# com.net
KiCad netlist of a schematic drawn in Altium Designer
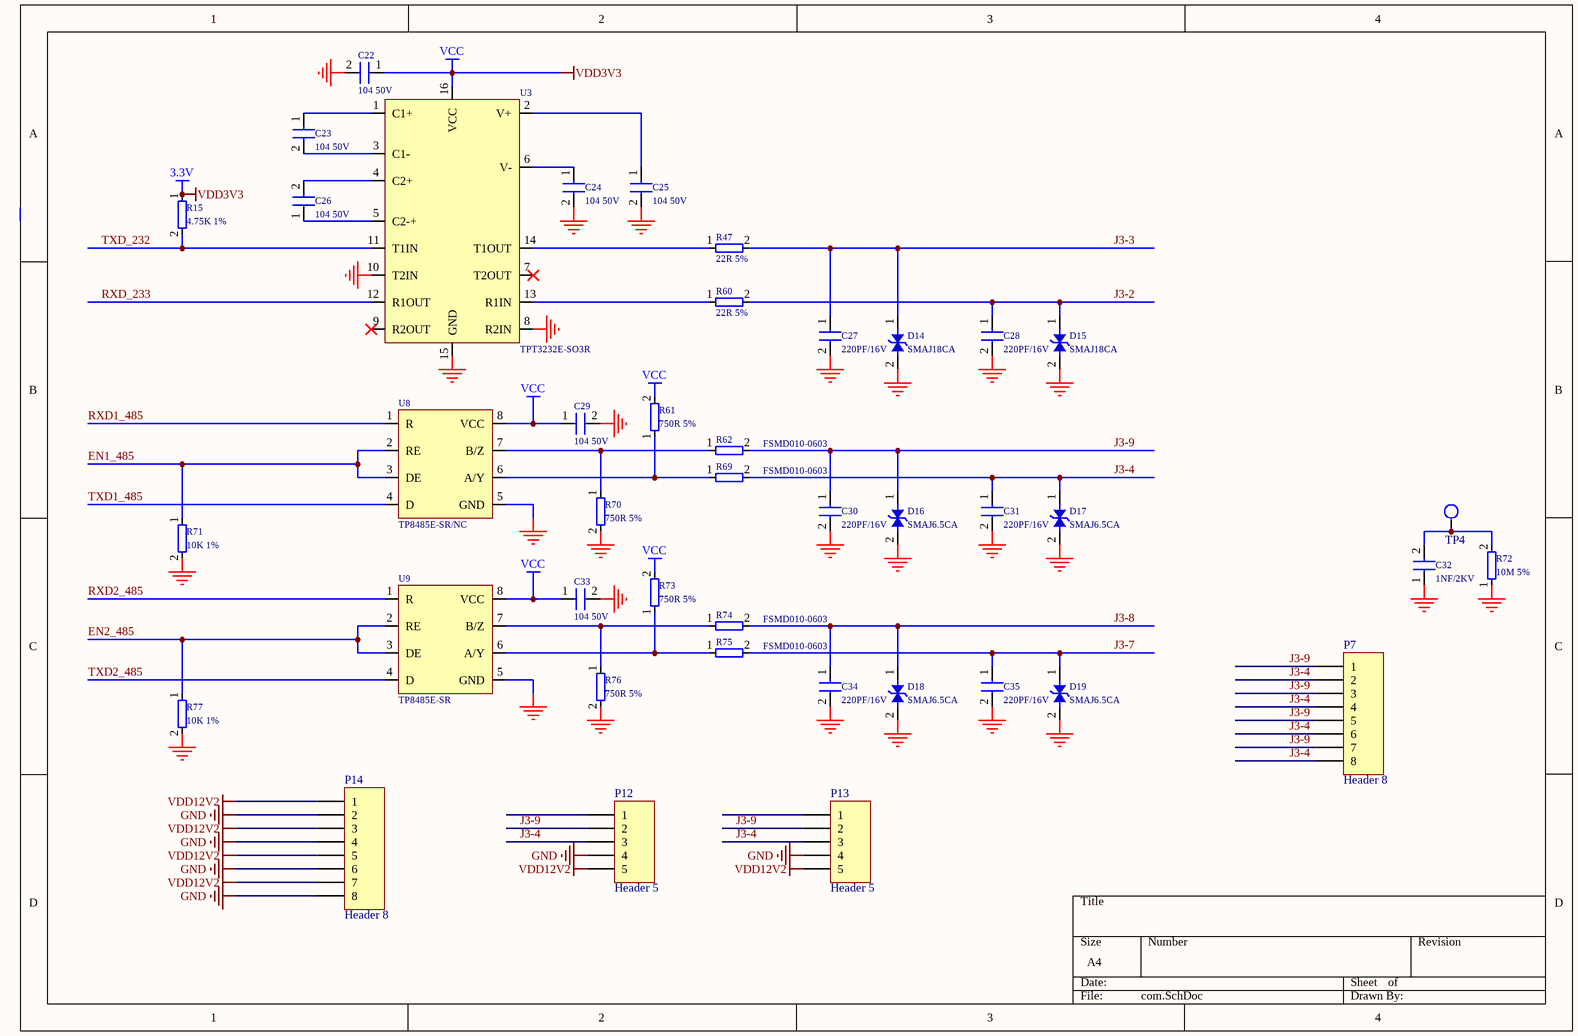
[diagram p0: com.SchDoc]

(export (version "E")
  (design (tool "Eeschema 10.0.6"))
  (components
    (comp (ref "C22") (value "104 50V") (footprint "0603C") (libsource (lib "*") (part "CAP")))
    (comp (ref "C23") (value "104 50V") (footprint "0603C") (libsource (lib "*") (part "CAP")))
    (comp (ref "C24") (value "104 50V") (footprint "0603C") (libsource (lib "*") (part "CAP")))
    (comp (ref "C25") (value "104 50V") (footprint "0603C") (libsource (lib "*") (part "CAP")))
    (comp (ref "C26") (value "104 50V") (footprint "0603C") (libsource (lib "*") (part "CAP")))
    (comp (ref "C27") (value "220PF/16V") (footprint "0603C") (libsource (lib "*") (part "CAP")))
    (comp (ref "C28") (value "220PF/16V") (footprint "0603C") (libsource (lib "*") (part "CAP")))
    (comp (ref "C29") (value "104 50V") (footprint "0603C") (libsource (lib "*") (part "CAP")))
    (comp (ref "C30") (value "220PF/16V") (footprint "0603C") (libsource (lib "*") (part "CAP")))
    (comp (ref "C31") (value "220PF/16V") (footprint "0603C") (libsource (lib "*") (part "CAP")))
    (comp (ref "C32") (value "1NF/2KV") (footprint "1206C") (libsource (lib "*") (part "CAP")))
    (comp (ref "C33") (value "104 50V") (footprint "0603C") (libsource (lib "*") (part "CAP")))
    (comp (ref "C34") (value "220PF/16V") (footprint "0603C") (libsource (lib "*") (part "CAP")))
    (comp (ref "C35") (value "220PF/16V") (footprint "0603C") (libsource (lib "*") (part "CAP")))
    (comp (ref "D14") (value "SMAJ18CA") (footprint "SMA") (libsource (lib "*") (part "D_ESD")))
    (comp (ref "D15") (value "SMAJ18CA") (footprint "SMA") (libsource (lib "*") (part "D_ESD")))
    (comp (ref "D16") (value "SMAJ6.5CA") (footprint "SMA") (libsource (lib "*") (part "D_ESD")))
    (comp (ref "D17") (value "SMAJ6.5CA") (footprint "SMA") (libsource (lib "*") (part "D_ESD")))
    (comp (ref "D18") (value "SMAJ6.5CA") (footprint "SMA") (libsource (lib "*") (part "D_ESD")))
    (comp (ref "D19") (value "SMAJ6.5CA") (footprint "SMA") (libsource (lib "*") (part "D_ESD")))
    (comp (ref "P7")
      (value "Header 8")
      (footprint "8X2.54MMZ")
      (description "Header, 8-Pin")
      (fields (field (name "PUBLISHER") "Altium Limited"))
      (libsource (lib "Miscellaneous Connectors") (part "Header 8"))
    )
    (comp (ref "P12")
      (value "Header 5")
      (footprint "5X2.54MMZ")
      (description "Header, 5-Pin")
      (fields (field (name "PUBLISHER") "Altium Limited"))
      (libsource (lib "Miscellaneous Connectors") (part "Header 5"))
    )
    (comp (ref "P13")
      (value "Header 5")
      (footprint "5X2.54MMZ")
      (description "Header, 5-Pin")
      (fields (field (name "PUBLISHER") "Altium Limited"))
      (libsource (lib "Miscellaneous Connectors") (part "Header 5"))
    )
    (comp (ref "P14")
      (value "Header 8")
      (footprint "电解模块主控板_V1.1_ZM_202109181:8X2.54MMZ")
      (description "Header, 8-Pin")
      (fields (field (name "PUBLISHER") "Altium Limited"))
      (libsource (lib "Miscellaneous Connectors") (part "Header 8"))
    )
    (comp (ref "R15") (value "4.75K 1%") (footprint "0603R") (libsource (lib "*") (part "RES")))
    (comp (ref "R47") (value "22R 5%") (footprint "0603R") (libsource (lib "*") (part "RES")))
    (comp (ref "R60") (value "22R 5%") (footprint "0603R") (libsource (lib "*") (part "RES")))
    (comp (ref "R61") (value "750R 5%") (footprint "0603R") (libsource (lib "*") (part "RES")))
    (comp (ref "R62") (value "FSMD010-0603") (footprint "0603R") (libsource (lib "*") (part "RES")))
    (comp (ref "R69") (value "FSMD010-0603") (footprint "0603R") (libsource (lib "*") (part "RES")))
    (comp (ref "R70") (value "750R 5%") (footprint "0603R") (libsource (lib "*") (part "RES")))
    (comp (ref "R71") (value "10K 1%") (footprint "0603R") (libsource (lib "*") (part "RES")))
    (comp (ref "R72") (value "10M 5%") (footprint "1206r") (libsource (lib "*") (part "RES")))
    (comp (ref "R73") (value "750R 5%") (footprint "0603R") (libsource (lib "*") (part "RES")))
    (comp (ref "R74") (value "FSMD010-0603") (footprint "0603R") (libsource (lib "*") (part "RES")))
    (comp (ref "R75") (value "FSMD010-0603") (footprint "0603R") (libsource (lib "*") (part "RES")))
    (comp (ref "R76") (value "750R 5%") (footprint "0603R") (libsource (lib "*") (part "RES")))
    (comp (ref "R77") (value "10K 1%") (footprint "0603R") (libsource (lib "*") (part "RES")))
    (comp (ref "TP4") (value "TPS") (footprint "tpd") (libsource (lib "stm32") (part "TPS")))
    (comp (ref "U3")
      (value "TPT3232E-SO3R")
      (footprint "SO-16Z")
      (libsource (lib "*") (part "TPT3232E-SO3R"))
    )
    (comp (ref "U8") (value "TP8485E-SR/NC") (footprint "SO-8") (libsource (lib "*") (part "TP8485E-SR")))
    (comp (ref "U9") (value "TP8485E-SR") (footprint "SO-8") (libsource (lib "*") (part "TP8485E-SR")))
  )
  (nets
    (net (code "1") (name "/EN1_485") (class "Default")
      (node (ref "R71") (pin "1") (pinfunction "1_1") (pintype "passive"))
      (node (ref "U8") (pin "2") (pinfunction "RE_2") (pintype "passive"))
      (node (ref "U8") (pin "3") (pinfunction "DE_3") (pintype "passive"))
    )
    (net (code "2") (name "/EN2_485") (class "Default")
      (node (ref "R77") (pin "1") (pinfunction "1_1") (pintype "passive"))
      (node (ref "U9") (pin "2") (pinfunction "RE_2") (pintype "passive"))
      (node (ref "U9") (pin "3") (pinfunction "DE_3") (pintype "passive"))
    )
    (net (code "3") (name "/J3-2") (class "Default")
      (node (ref "C28") (pin "1") (pintype "passive"))
      (node (ref "D15") (pin "1") (pintype "passive"))
      (node (ref "R60") (pin "2") (pinfunction "2_2") (pintype "passive"))
    )
    (net (code "4") (name "/J3-3") (class "Default")
      (node (ref "C27") (pin "1") (pintype "passive"))
      (node (ref "D14") (pin "1") (pintype "passive"))
      (node (ref "R47") (pin "2") (pinfunction "2_2") (pintype "passive"))
    )
    (net (code "5") (name "/J3-4") (class "Default")
      (node (ref "C31") (pin "1") (pintype "passive"))
      (node (ref "D17") (pin "1") (pintype "passive"))
      (node (ref "P12") (pin "3") (pinfunction "3_3") (pintype "passive"))
      (node (ref "P13") (pin "3") (pinfunction "3_3") (pintype "passive"))
      (node (ref "P7") (pin "2") (pinfunction "2_2") (pintype "passive"))
      (node (ref "P7") (pin "4") (pinfunction "4_4") (pintype "passive"))
      (node (ref "P7") (pin "6") (pinfunction "6_6") (pintype "passive"))
      (node (ref "P7") (pin "8") (pinfunction "8_8") (pintype "passive"))
      (node (ref "R69") (pin "2") (pinfunction "2_2") (pintype "passive"))
    )
    (net (code "6") (name "/J3-7") (class "Default")
      (node (ref "C35") (pin "1") (pintype "passive"))
      (node (ref "D19") (pin "1") (pintype "passive"))
      (node (ref "R75") (pin "2") (pinfunction "2_2") (pintype "passive"))
    )
    (net (code "7") (name "/J3-8") (class "Default")
      (node (ref "C34") (pin "1") (pintype "passive"))
      (node (ref "D18") (pin "1") (pintype "passive"))
      (node (ref "R74") (pin "2") (pinfunction "2_2") (pintype "passive"))
    )
    (net (code "8") (name "/J3-9") (class "Default")
      (node (ref "C30") (pin "1") (pintype "passive"))
      (node (ref "D16") (pin "1") (pintype "passive"))
      (node (ref "P12") (pin "2") (pinfunction "2_2") (pintype "passive"))
      (node (ref "P13") (pin "2") (pinfunction "2_2") (pintype "passive"))
      (node (ref "P7") (pin "1") (pinfunction "1_1") (pintype "passive"))
      (node (ref "P7") (pin "3") (pinfunction "3_3") (pintype "passive"))
      (node (ref "P7") (pin "5") (pinfunction "5_5") (pintype "passive"))
      (node (ref "P7") (pin "7") (pinfunction "7_7") (pintype "passive"))
      (node (ref "R62") (pin "2") (pinfunction "2_2") (pintype "passive"))
    )
    (net (code "9") (name "/RXD1_485") (class "Default")
      (node (ref "U8") (pin "1") (pinfunction "R_1") (pintype "passive"))
    )
    (net (code "10") (name "/RXD2_485") (class "Default")
      (node (ref "U9") (pin "1") (pinfunction "R_1") (pintype "passive"))
    )
    (net (code "11") (name "/RXD_233") (class "Default")
      (node (ref "U3") (pin "12") (pinfunction "R1OUT_12") (pintype "passive"))
    )
    (net (code "12") (name "/TXD1_485") (class "Default")
      (node (ref "U8") (pin "4") (pinfunction "D_4") (pintype "passive"))
    )
    (net (code "13") (name "/TXD2_485") (class "Default")
      (node (ref "U9") (pin "4") (pinfunction "D_4") (pintype "passive"))
    )
    (net (code "14") (name "/TXD_232") (class "Default")
      (node (ref "R15") (pin "2") (pinfunction "2_2") (pintype "passive"))
      (node (ref "U3") (pin "11") (pinfunction "T1IN_11") (pintype "passive"))
    )
    (net (code "15") (name "3.3V") (class "Default")
      (node (ref "C22") (pin "1") (pintype "passive"))
      (node (ref "C29") (pin "1") (pintype "passive"))
      (node (ref "C33") (pin "1") (pintype "passive"))
      (node (ref "R15") (pin "1") (pinfunction "1_1") (pintype "passive"))
      (node (ref "R61") (pin "2") (pinfunction "2_2") (pintype "passive"))
      (node (ref "R73") (pin "2") (pinfunction "2_2") (pintype "passive"))
      (node (ref "U3") (pin "16") (pinfunction "VCC_16") (pintype "passive"))
      (node (ref "U8") (pin "8") (pinfunction "VCC_8") (pintype "passive"))
      (node (ref "U9") (pin "8") (pinfunction "VCC_8") (pintype "passive"))
    )
    (net (code "16") (name "GND") (class "Default")
      (node (ref "C22") (pin "2") (pintype "passive"))
      (node (ref "C24") (pin "2") (pintype "passive"))
      (node (ref "C25") (pin "2") (pintype "passive"))
      (node (ref "C27") (pin "2") (pintype "passive"))
      (node (ref "C28") (pin "2") (pintype "passive"))
      (node (ref "C29") (pin "2") (pintype "passive"))
      (node (ref "C30") (pin "2") (pintype "passive"))
      (node (ref "C31") (pin "2") (pintype "passive"))
      (node (ref "C32") (pin "1") (pintype "passive"))
      (node (ref "C33") (pin "2") (pintype "passive"))
      (node (ref "C34") (pin "2") (pintype "passive"))
      (node (ref "C35") (pin "2") (pintype "passive"))
      (node (ref "D14") (pin "2") (pintype "passive"))
      (node (ref "D15") (pin "2") (pintype "passive"))
      (node (ref "D16") (pin "2") (pintype "passive"))
      (node (ref "D17") (pin "2") (pintype "passive"))
      (node (ref "D18") (pin "2") (pintype "passive"))
      (node (ref "D19") (pin "2") (pintype "passive"))
      (node (ref "P12") (pin "4") (pinfunction "4_4") (pintype "passive"))
      (node (ref "P13") (pin "4") (pinfunction "4_4") (pintype "passive"))
      (node (ref "P14") (pin "2") (pinfunction "2_2") (pintype "passive"))
      (node (ref "P14") (pin "4") (pinfunction "4_4") (pintype "passive"))
      (node (ref "P14") (pin "6") (pinfunction "6_6") (pintype "passive"))
      (node (ref "P14") (pin "8") (pinfunction "8_8") (pintype "passive"))
      (node (ref "R70") (pin "2") (pinfunction "2_2") (pintype "passive"))
      (node (ref "R71") (pin "2") (pinfunction "2_2") (pintype "passive"))
      (node (ref "R72") (pin "1") (pinfunction "1_1") (pintype "passive"))
      (node (ref "R76") (pin "2") (pinfunction "2_2") (pintype "passive"))
      (node (ref "R77") (pin "2") (pinfunction "2_2") (pintype "passive"))
      (node (ref "U3") (pin "10") (pinfunction "T2IN_10") (pintype "passive"))
      (node (ref "U3") (pin "15") (pinfunction "GND_15") (pintype "passive"))
      (node (ref "U3") (pin "8") (pinfunction "R2IN_8") (pintype "passive"))
      (node (ref "U8") (pin "5") (pinfunction "GND_5") (pintype "passive"))
      (node (ref "U9") (pin "5") (pinfunction "GND_5") (pintype "passive"))
    )
    (net (code "17") (name "Net-(C32-Pad2)") (class "Default")
      (node (ref "C32") (pin "2") (pintype "passive"))
      (node (ref "R72") (pin "2") (pinfunction "2_2") (pintype "passive"))
      (node (ref "TP4") (pin "1") (pinfunction "1_1") (pintype "passive"))
    )
    (net (code "18") (name "Net-(U3-C1+)") (class "Default")
      (node (ref "C23") (pin "1") (pintype "passive"))
      (node (ref "U3") (pin "1") (pinfunction "C1+_1") (pintype "passive"))
    )
    (net (code "19") (name "Net-(U3-C1-)") (class "Default")
      (node (ref "C23") (pin "2") (pintype "passive"))
      (node (ref "U3") (pin "3") (pinfunction "C1-_3") (pintype "passive"))
    )
    (net (code "20") (name "Net-(U3-C2+)") (class "Default")
      (node (ref "C26") (pin "2") (pintype "passive"))
      (node (ref "U3") (pin "4") (pinfunction "C2+_4") (pintype "passive"))
    )
    (net (code "21") (name "Net-(U3-C2-+)") (class "Default")
      (node (ref "C26") (pin "1") (pintype "passive"))
      (node (ref "U3") (pin "5") (pinfunction "C2-+_5") (pintype "passive"))
    )
    (net (code "22") (name "Net-(U3-R1IN)") (class "Default")
      (node (ref "R60") (pin "1") (pinfunction "1_1") (pintype "passive"))
      (node (ref "U3") (pin "13") (pinfunction "R1IN_13") (pintype "passive"))
    )
    (net (code "23") (name "Net-(U3-T1OUT)") (class "Default")
      (node (ref "R47") (pin "1") (pinfunction "1_1") (pintype "passive"))
      (node (ref "U3") (pin "14") (pinfunction "T1OUT_14") (pintype "passive"))
    )
    (net (code "24") (name "Net-(U3-V+)") (class "Default")
      (node (ref "C25") (pin "1") (pintype "passive"))
      (node (ref "U3") (pin "2") (pinfunction "V+_2") (pintype "passive"))
    )
    (net (code "25") (name "Net-(U3-V-)") (class "Default")
      (node (ref "C24") (pin "1") (pintype "passive"))
      (node (ref "U3") (pin "6") (pinfunction "V-_6") (pintype "passive"))
    )
    (net (code "26") (name "Net-(U8-A{slash}Y)") (class "Default")
      (node (ref "R61") (pin "1") (pinfunction "1_1") (pintype "passive"))
      (node (ref "R69") (pin "1") (pinfunction "1_1") (pintype "passive"))
      (node (ref "U8") (pin "6") (pinfunction "A/Y_6") (pintype "passive"))
    )
    (net (code "27") (name "Net-(U8-B{slash}Z)") (class "Default")
      (node (ref "R62") (pin "1") (pinfunction "1_1") (pintype "passive"))
      (node (ref "R70") (pin "1") (pinfunction "1_1") (pintype "passive"))
      (node (ref "U8") (pin "7") (pinfunction "B/Z_7") (pintype "passive"))
    )
    (net (code "28") (name "Net-(U9-A{slash}Y)") (class "Default")
      (node (ref "R73") (pin "1") (pinfunction "1_1") (pintype "passive"))
      (node (ref "R75") (pin "1") (pinfunction "1_1") (pintype "passive"))
      (node (ref "U9") (pin "6") (pinfunction "A/Y_6") (pintype "passive"))
    )
    (net (code "29") (name "Net-(U9-B{slash}Z)") (class "Default")
      (node (ref "R74") (pin "1") (pinfunction "1_1") (pintype "passive"))
      (node (ref "R76") (pin "1") (pinfunction "1_1") (pintype "passive"))
      (node (ref "U9") (pin "7") (pinfunction "B/Z_7") (pintype "passive"))
    )
    (net (code "30") (name "VDD12V2") (class "Default")
      (node (ref "P12") (pin "5") (pinfunction "5_5") (pintype "passive"))
      (node (ref "P13") (pin "5") (pinfunction "5_5") (pintype "passive"))
      (node (ref "P14") (pin "1") (pinfunction "1_1") (pintype "passive"))
      (node (ref "P14") (pin "3") (pinfunction "3_3") (pintype "passive"))
      (node (ref "P14") (pin "5") (pinfunction "5_5") (pintype "passive"))
      (node (ref "P14") (pin "7") (pinfunction "7_7") (pintype "passive"))
    )
    (net (code "31") (name "unconnected-(P12-Pad1)") (class "Default")
      (node (ref "P12") (pin "1") (pinfunction "1_1") (pintype "passive"))
    )
    (net (code "32") (name "unconnected-(P13-Pad1)") (class "Default")
      (node (ref "P13") (pin "1") (pinfunction "1_1") (pintype "passive"))
    )
    (net (code "33") (name "unconnected-(U3-R2OUT-Pad9)") (class "Default")
      (node (ref "U3") (pin "9") (pinfunction "R2OUT_9") (pintype "passive+no_connect"))
    )
    (net (code "34") (name "unconnected-(U3-T2OUT-Pad7)") (class "Default")
      (node (ref "U3") (pin "7") (pinfunction "T2OUT_7") (pintype "passive+no_connect"))
    )
  )
)
